# MIXR_Power_-_Regulators.net
KiCad netlist of a schematic drawn in Altium Designer
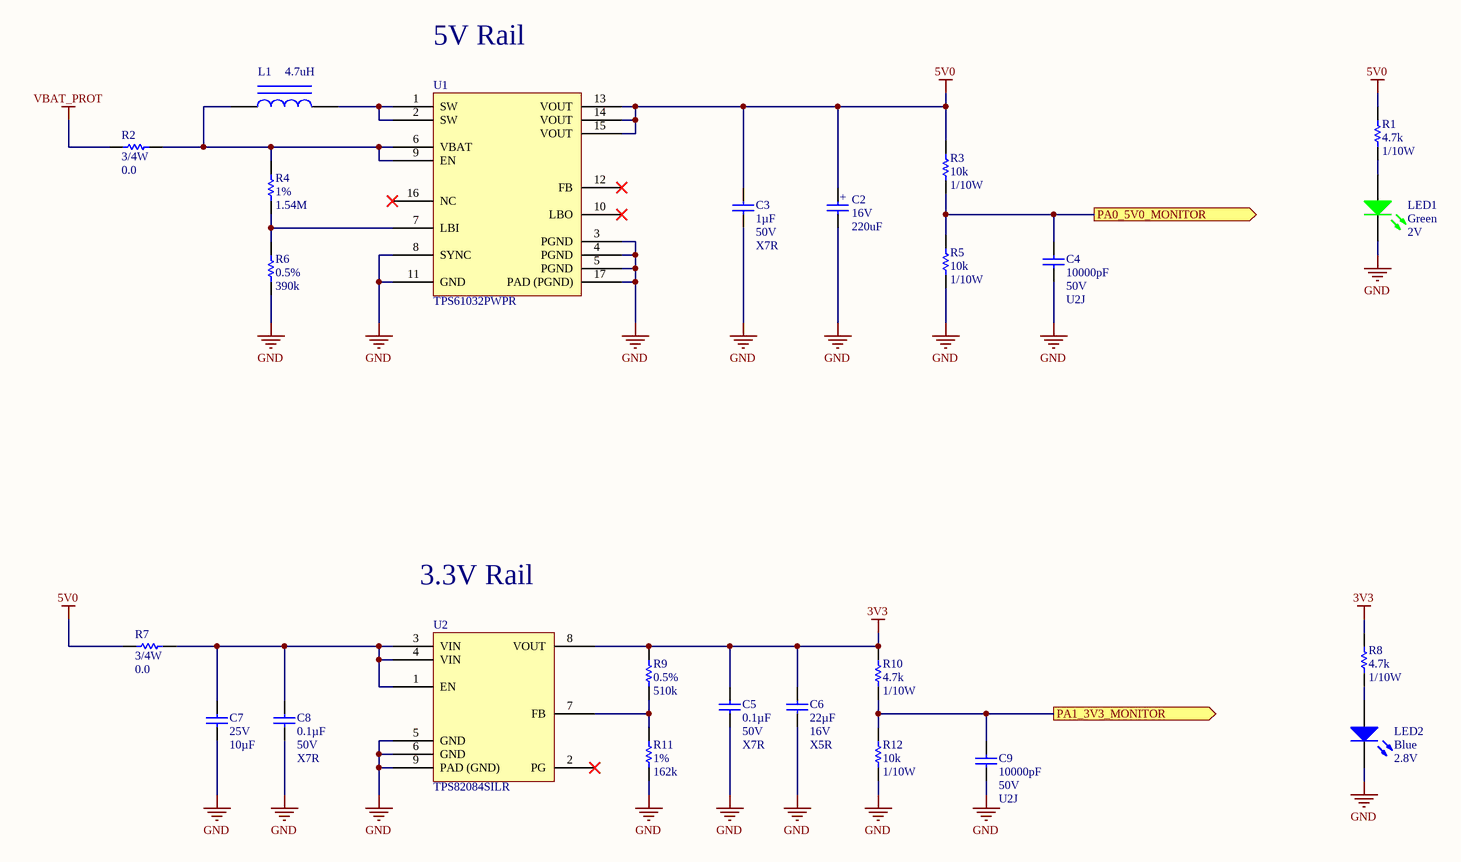
[diagram p0: MIXR Power - Regulators.SchDoc]

(export (version "E")
  (design (tool "Eeschema 10.0.6"))
  (components
    (comp (ref "C2")
      (value "CAP ALUM 220UF 20% 16V SMD")
      (footprint "CAP ALUM 6.3MM RADIAL SMD")
      (description "220µF 16V Aluminum Electrolytic Capacitors Radial, Can - SMD 2000 Hrs @ 85°C")
      (fields
        (field (name "MANUFACTURER") "Panasonic")
        (field (name "TOLERANCE") "20%")
        (field (name "VOLTAGE") "16V")
        (field (name "CAPACITANCE") "220uF")
      )
      (libsource (lib "Schematic Diagrams") (part "CAP ALUM 220UF 20% 16V SMD"))
    )
    (comp (ref "C3")
      (value "CAP CER 1UF 50V 10% X7R 0603")
      (footprint "CAP, 0603")
      (description "1µF ±10% 50V Ceramic Capacitor X7R 0603 (1608 Metric)")
      (fields
        (field (name "TOLERANCE") "±10%")
        (field (name "CAPACITANCE") "1µF")
        (field (name "VOLTAGE") "50V")
        (field (name "TEMPERATURE COEFFICIENT") "X7R")
      )
      (libsource (lib "Schematic Diagrams") (part "CAP CER 1UF 50V 10% X7R 0603"))
    )
    (comp (ref "C4")
      (value "CAP CER 10nF 50V 5% X7R 0603")
      (footprint "CAP, 0603")
      (description "10000pF ±5% 50V Ceramic Capacitor U2J 0603 (1608 Metric)")
      (fields
        (field (name "TOLERANCE") "±5%")
        (field (name "CAPACITANCE") "10000pF")
        (field (name "VOLTAGE") "50V")
        (field (name "TEMPERATURE COEFFICIENT") "U2J")
      )
      (libsource (lib "Schematic Diagrams") (part "CAP CER 10nF 50V 5% X7R 0603"))
    )
    (comp (ref "C5")
      (value "CAP CER 0.1UF 50V 10% X7R 0603")
      (footprint "CAP, 0603")
      (description "0.10µF ±10% 50V Ceramic Capacitor X7R 0603 (1608 Metric)")
      (fields
        (field (name "TOLERANCE") "±10%")
        (field (name "CAPACITANCE") "0.1µF")
        (field (name "VOLTAGE") "50V")
        (field (name "TEMPERATURE COEFFICIENT") "X7R")
      )
      (libsource (lib "Schematic Diagrams") (part "CAP CER 0.1UF 50V 10% X7R 0603"))
    )
    (comp (ref "C6")
      (value "CAP CER 22UF 16V ±20% X5R 1210")
      (footprint "CAP, 1210")
      (description "22µF ±20% 16V Ceramic Capacitor X5R 1210 (3225 Metric)")
      (fields
        (field (name "TOLERANCE") "±20%")
        (field (name "CAPACITANCE") "22µF")
        (field (name "VOLTAGE") "16V")
        (field (name "TEMPERATURE COEFFICIENT") "X5R")
      )
      (libsource (lib "Schematic Diagrams") (part "CAP CER 22UF 16V ±20% X5R 1210"))
    )
    (comp (ref "C7")
      (value "CAP CER 10uF 25V 10% X5R 0805")
      (footprint "CAP, 0805")
      (description "10µF ±10% 25V Ceramic Capacitor X5R 0805 (2012 Metric)")
      (fields
        (field (name "MANUFACTURER") "Murata Electronics North America")
        (field (name "MANUFACTURER PART NUMBER") "GRM21BR61E106KA73L")
        (field (name "VOLTAGE - RATED") "25V")
        (field (name "CAPACITANCE") "10µF")
      )
      (libsource (lib "Schematic Diagrams") (part "CAP CER 10uF 25V 10% X5R 0805"))
    )
    (comp (ref "C8")
      (value "CAP CER 0.1UF 50V 10% X7R 0603")
      (footprint "CAP, 0603")
      (description "0.10µF ±10% 50V Ceramic Capacitor X7R 0603 (1608 Metric)")
      (fields
        (field (name "TOLERANCE") "±10%")
        (field (name "CAPACITANCE") "0.1µF")
        (field (name "VOLTAGE") "50V")
        (field (name "TEMPERATURE COEFFICIENT") "X7R")
      )
      (libsource (lib "Schematic Diagrams") (part "CAP CER 0.1UF 50V 10% X7R 0603"))
    )
    (comp (ref "C9")
      (value "CAP CER 10nF 50V 5% X7R 0603")
      (footprint "CAP, 0603")
      (description "10000pF ±5% 50V Ceramic Capacitor U2J 0603 (1608 Metric)")
      (fields
        (field (name "TOLERANCE") "±5%")
        (field (name "CAPACITANCE") "10000pF")
        (field (name "VOLTAGE") "50V")
        (field (name "TEMPERATURE COEFFICIENT") "U2J")
      )
      (libsource (lib "Schematic Diagrams") (part "CAP CER 10nF 50V 5% X7R 0603"))
    )
    (comp (ref "L1")
      (value "IND 4.7uH 9.4A 10% SMD")
      (footprint "IND 4.7uH 9.4A 10% SMD")
      (description "Fixed Inductors SER1360 High Current 4.7 uH 10 % 9.4 A")
      (fields
        (field (name "MANUFACTURER") "Coilcraft")
        (field (name "TOLERANCE") "10%")
        (field (name "INDUCTANCE") "4.7uH")
      )
      (libsource (lib "Schematic Diagrams") (part "IND 4.7uH 9.4A 10% SMD"))
    )
    (comp (ref "LED1")
      (value "LED GREEN CLEAR 2V 0603")
      (footprint "LED_0603")
      (description "Green 572nm LED Indication - Discrete 2V 0603 (1608 Metric)")
      (fields
        (field (name "MANUFACTURER") "Wurth Electronics Inc.")
        (field (name "MANUFACTURER PART NUMBER") "150060VS75000")
        (field (name "COLOR") "Green")
        (field (name "VOLTAGE - FORWARD (VF) (TYP)") "2V")
      )
      (libsource (lib "Schematic Diagrams") (part "LED GREEN CLEAR 2V 0603"))
    )
    (comp (ref "LED2")
      (value "LED BLUE CLEAR 2.8V 0603")
      (footprint "LED_0603")
      (description "Blue 470nm LED Indication - Discrete 2.8V 0603 (1608 Metric)")
      (fields (field (name "COLOR") "Blue") (field (name "VOLTAGE - FORWARD (VF) (TYP)") "2.8V"))
      (libsource (lib "Schematic Diagrams") (part "LED BLUE CLEAR 2.8V 0603"))
    )
    (comp (ref "R1")
      (value "RES 4.7K OHM 1% 1/10W 0603")
      (footprint "RES, 0603")
      (description "4.7k Ohm ±1% 0.1W, 1/10W Chip Resistor 0603 (1608 Metric) Moisture Resistant Thick Film")
      (fields
        (field (name "TOLERANCE") "±1%")
        (field (name "RESISTANCE (OHMS)") "4.7k")
        (field (name "POWER (WATTS)") "1/10W")
      )
      (libsource (lib "Schematic Diagrams") (part "RES 4.7K OHM 1% 1/10W 0603"))
    )
    (comp (ref "R2")
      (value "RES 0.0 OHM 3/4W 1206")
      (footprint "RES 1206")
      (description "0 Ohms Jumper 0.75W, 3/4W Chip Resistor 1206 (3216 Metric) Automotive AEC-Q200 Metal Foil")
      (fields
        (field (name "MANUFACTURER") "Stackpole Electronics Inc.")
        (field (name "MANUFACTURER PART NUMBER") "HCJ1206ZT0R00")
        (field (name "POWER (WATTS)") "3/4W")
        (field (name "RESISTANCE") "0.0")
      )
      (libsource (lib "Schematic Diagrams") (part "RES 0.0 OHM 3/4W 1206"))
    )
    (comp (ref "R3")
      (value "RES 10K OHM 1% 1/10W 0603")
      (footprint "RES, 0603")
      (description "RES SMD 10K OHM 1% 1/10W 0603")
      (fields
        (field (name "TOLERANCE") "±1%")
        (field (name "RESISTANCE") "10k")
        (field (name "POWER") "1/10W")
      )
      (libsource (lib "Schematic Diagrams") (part "RES 10K OHM 1% 1/10W 0603"))
    )
    (comp (ref "R4")
      (value "RES 1.54M OHM 1% 1/10W 0603")
      (footprint "RES, 0603")
      (fields
        (field (name "MANUFACTURER") "Vishay")
        (field (name "MANUFACTURER PART NUMBER") "CRCW06031M54FKEA")
        (field (name "TOLERANCE") "1%")
        (field (name "RESISTANCE") "1.54M")
      )
      (libsource (lib "Schematic Diagrams") (part "RES 1.54M OHM 1% 1/10W 0603"))
    )
    (comp (ref "R5")
      (value "RES 10K OHM 1% 1/10W 0603")
      (footprint "RES, 0603")
      (description "RES SMD 10K OHM 1% 1/10W 0603")
      (fields
        (field (name "TOLERANCE") "±1%")
        (field (name "RESISTANCE") "10k")
        (field (name "POWER") "1/10W")
      )
      (libsource (lib "Schematic Diagrams") (part "RES 10K OHM 1% 1/10W 0603"))
    )
    (comp (ref "R6")
      (value "RES 390K OHM 1% 1/10W 0603")
      (footprint "RES, 0603")
      (description "390 kOhms ±0.5% 0.1W, 1/10W Chip Resistor 0603 (1608 Metric) Thin Film")
      (fields
        (field (name "MANUFACTURER") "Yageo")
        (field (name "MANUFACTURER PART NUMBER") "RT0603DRE07390KL")
        (field (name "TOLERANCE") "0.5%")
        (field (name "RESISTANCE") "390k")
      )
      (libsource (lib "Schematic Diagrams") (part "RES 390K OHM 1% 1/10W 0603"))
    )
    (comp (ref "R7")
      (value "RES 0.0 OHM 3/4W 1206")
      (footprint "RES 1206")
      (description "0 Ohms Jumper 0.75W, 3/4W Chip Resistor 1206 (3216 Metric) Automotive AEC-Q200 Metal Foil")
      (fields
        (field (name "MANUFACTURER") "Stackpole Electronics Inc.")
        (field (name "MANUFACTURER PART NUMBER") "HCJ1206ZT0R00")
        (field (name "POWER (WATTS)") "3/4W")
        (field (name "RESISTANCE") "0.0")
      )
      (libsource (lib "Schematic Diagrams") (part "RES 0.0 OHM 3/4W 1206"))
    )
    (comp (ref "R8")
      (value "RES 4.7K OHM 1% 1/10W 0603")
      (footprint "RES, 0603")
      (description "4.7k Ohm ±1% 0.1W, 1/10W Chip Resistor 0603 (1608 Metric) Moisture Resistant Thick Film")
      (fields
        (field (name "TOLERANCE") "±1%")
        (field (name "RESISTANCE (OHMS)") "4.7k")
        (field (name "POWER (WATTS)") "1/10W")
      )
      (libsource (lib "Schematic Diagrams") (part "RES 4.7K OHM 1% 1/10W 0603"))
    )
    (comp (ref "R9")
      (value "RES 510K OHM 0.5% 1/10W 0603")
      (footprint "RES, 0603")
      (description "510 kOhms ±0.5% 0.1W, 1/10W Chip Resistor 0603 (1608 Metric) Thin Film")
      (fields
        (field (name "MANUFACTURER") "Yageo")
        (field (name "MANUFACTURER PART NUMBER") "RT0603DRE07510KL")
        (field (name "TOLERANCE") "0.5%")
        (field (name "RESISTANCE") "510k")
      )
      (libsource (lib "Schematic Diagrams") (part "RES 510K OHM 0.5% 1/10W 0603"))
    )
    (comp (ref "R10")
      (value "RES 4.7K OHM 1% 1/10W 0603")
      (footprint "RES, 0603")
      (description "4.7k Ohm ±1% 0.1W, 1/10W Chip Resistor 0603 (1608 Metric) Moisture Resistant Thick Film")
      (fields
        (field (name "TOLERANCE") "±1%")
        (field (name "RESISTANCE (OHMS)") "4.7k")
        (field (name "POWER (WATTS)") "1/10W")
      )
      (libsource (lib "Schematic Diagrams") (part "RES 4.7K OHM 1% 1/10W 0603"))
    )
    (comp (ref "R11")
      (value "RES 162K OHM 1% 1/10W 0603")
      (footprint "RES, 0603")
      (description "162 kOhms ±1% 0.1W, 1/10W Chip Resistor 0603 (1608 Metric) Moisture Resistant Thick Film")
      (fields
        (field (name "MANUFACTURER") "Yageo")
        (field (name "MANUFACTURER PART NUMBER") "RC0603FR-07162KL")
        (field (name "TOLERANCE") "1%")
        (field (name "RESISTANCE") "162k")
      )
      (libsource (lib "Schematic Diagrams") (part "RES 162K OHM 1% 1/10W 0603"))
    )
    (comp (ref "R12")
      (value "RES 10K OHM 1% 1/10W 0603")
      (footprint "RES, 0603")
      (description "RES SMD 10K OHM 1% 1/10W 0603")
      (fields
        (field (name "TOLERANCE") "±1%")
        (field (name "RESISTANCE") "10k")
        (field (name "POWER") "1/10W")
      )
      (libsource (lib "Schematic Diagrams") (part "RES 10K OHM 1% 1/10W 0603"))
    )
    (comp (ref "U1")
      (value "IC REG BOOST 5V 3.6A 16-TSSOP")
      (footprint "IC REG BOOST 5V 3.6A 16-TSSOP")
      (fields
        (field (name "MANUFACTURER") "Texas Instruments")
        (field (name "MANUFACTURER PART NUMBER") "TPS61032PWPR")
      )
      (libsource (lib "Schematic Diagrams") (part "IC REG BOOST 5V 3.6A 16-TSSOP"))
    )
    (comp (ref "U2")
      (value "IC DCDC 0.8-6V 2A 8-uSIP")
      (footprint "IC DCDC 0.8-6V 2A 8-uSIP")
      (description "Non-Isolated PoL Module DC DC Converter 1 Output 0.8 ~ 6V 2A 2.5V - 6V Input")
      (fields
        (field (name "MANUFACTURER") "Texas Instruments")
        (field (name "MANUFACTURER PART NUMBER") "TPS82084SILR")
      )
      (libsource (lib "Schematic Diagrams") (part "IC DCDC 0.8-6V 2A 8-uSIP"))
    )
  )
  (nets
    (net (code "1") (name "/PA0_5V0_MONITOR") (class "Default")
      (node (ref "C4") (pin "1") (pinfunction "1_1") (pintype "passive"))
      (node (ref "R3") (pin "2") (pinfunction "2_2") (pintype "passive"))
      (node (ref "R5") (pin "1") (pinfunction "1_1") (pintype "passive"))
    )
    (net (code "2") (name "/PA1_3V3_MONITOR") (class "Default")
      (node (ref "C9") (pin "1") (pinfunction "1_1") (pintype "passive"))
      (node (ref "R10") (pin "2") (pinfunction "2_2") (pintype "passive"))
      (node (ref "R12") (pin "1") (pinfunction "1_1") (pintype "passive"))
    )
    (net (code "3") (name "3V3") (class "Default")
      (node (ref "C5") (pin "1") (pinfunction "1_1") (pintype "passive"))
      (node (ref "C6") (pin "1") (pinfunction "1_1") (pintype "passive"))
      (node (ref "R10") (pin "1") (pinfunction "1_1") (pintype "passive"))
      (node (ref "R8") (pin "1") (pinfunction "1_1") (pintype "passive"))
      (node (ref "R9") (pin "1") (pinfunction "1_1") (pintype "passive"))
      (node (ref "U2") (pin "8") (pinfunction "VOUT_8") (pintype "passive"))
    )
    (net (code "4") (name "5V0") (class "Default")
      (node (ref "C2") (pin "1") (pinfunction "1_1") (pintype "passive"))
      (node (ref "C3") (pin "1") (pinfunction "1_1") (pintype "passive"))
      (node (ref "R1") (pin "1") (pinfunction "1_1") (pintype "passive"))
      (node (ref "R3") (pin "1") (pinfunction "1_1") (pintype "passive"))
      (node (ref "R7") (pin "1") (pinfunction "1_1") (pintype "passive"))
      (node (ref "U1") (pin "13") (pinfunction "VOUT_13") (pintype "passive"))
      (node (ref "U1") (pin "14") (pinfunction "VOUT_14") (pintype "passive"))
      (node (ref "U1") (pin "15") (pinfunction "VOUT_15") (pintype "passive"))
    )
    (net (code "5") (name "GND") (class "Default")
      (node (ref "C2") (pin "2") (pinfunction "2_2") (pintype "passive"))
      (node (ref "C3") (pin "2") (pinfunction "2_2") (pintype "passive"))
      (node (ref "C4") (pin "2") (pinfunction "2_2") (pintype "passive"))
      (node (ref "C5") (pin "2") (pinfunction "2_2") (pintype "passive"))
      (node (ref "C6") (pin "2") (pinfunction "2_2") (pintype "passive"))
      (node (ref "C7") (pin "2") (pinfunction "2_2") (pintype "passive"))
      (node (ref "C8") (pin "2") (pinfunction "2_2") (pintype "passive"))
      (node (ref "C9") (pin "2") (pinfunction "2_2") (pintype "passive"))
      (node (ref "LED1") (pin "2") (pinfunction "K_2") (pintype "passive"))
      (node (ref "LED2") (pin "2") (pinfunction "K_2") (pintype "passive"))
      (node (ref "R11") (pin "2") (pinfunction "2_2") (pintype "passive"))
      (node (ref "R12") (pin "2") (pinfunction "2_2") (pintype "passive"))
      (node (ref "R5") (pin "2") (pinfunction "2_2") (pintype "passive"))
      (node (ref "R6") (pin "2") (pinfunction "2_2") (pintype "passive"))
      (node (ref "U1") (pin "11") (pinfunction "GND_11") (pintype "passive"))
      (node (ref "U1") (pin "17") (pinfunction "PAD_(PGND)_17") (pintype "passive"))
      (node (ref "U1") (pin "3") (pinfunction "PGND_3") (pintype "passive"))
      (node (ref "U1") (pin "4") (pinfunction "PGND_4") (pintype "passive"))
      (node (ref "U1") (pin "5") (pinfunction "PGND_5") (pintype "passive"))
      (node (ref "U1") (pin "8") (pinfunction "SYNC_8") (pintype "passive"))
      (node (ref "U2") (pin "5") (pinfunction "GND_5") (pintype "passive"))
      (node (ref "U2") (pin "6") (pinfunction "GND_6") (pintype "passive"))
      (node (ref "U2") (pin "9") (pinfunction "PAD_(GND)_9") (pintype "passive"))
    )
    (net (code "6") (name "Net-(L1-Pad2)") (class "Default")
      (node (ref "L1") (pin "2") (pinfunction "2_2") (pintype "passive"))
      (node (ref "U1") (pin "1") (pinfunction "SW_1") (pintype "passive"))
      (node (ref "U1") (pin "2") (pinfunction "SW_2") (pintype "passive"))
    )
    (net (code "7") (name "Net-(LED1-A)") (class "Default")
      (node (ref "LED1") (pin "1") (pinfunction "A_1") (pintype "passive"))
      (node (ref "R1") (pin "2") (pinfunction "2_2") (pintype "passive"))
    )
    (net (code "8") (name "Net-(LED2-A)") (class "Default")
      (node (ref "LED2") (pin "1") (pinfunction "A_1") (pintype "passive"))
      (node (ref "R8") (pin "2") (pinfunction "2_2") (pintype "passive"))
    )
    (net (code "9") (name "Net-(U1-EN)") (class "Default")
      (node (ref "L1") (pin "1") (pinfunction "1_1") (pintype "passive"))
      (node (ref "R2") (pin "2") (pinfunction "2_2") (pintype "passive"))
      (node (ref "R4") (pin "1") (pinfunction "1_1") (pintype "passive"))
      (node (ref "U1") (pin "6") (pinfunction "VBAT_6") (pintype "passive"))
      (node (ref "U1") (pin "9") (pinfunction "EN_9") (pintype "passive"))
    )
    (net (code "10") (name "Net-(U1-LBI)") (class "Default")
      (node (ref "R4") (pin "2") (pinfunction "2_2") (pintype "passive"))
      (node (ref "R6") (pin "1") (pinfunction "1_1") (pintype "passive"))
      (node (ref "U1") (pin "7") (pinfunction "LBI_7") (pintype "passive"))
    )
    (net (code "11") (name "Net-(U2-EN)") (class "Default")
      (node (ref "C7") (pin "1") (pinfunction "1_1") (pintype "passive"))
      (node (ref "C8") (pin "1") (pinfunction "1_1") (pintype "passive"))
      (node (ref "R7") (pin "2") (pinfunction "2_2") (pintype "passive"))
      (node (ref "U2") (pin "1") (pinfunction "EN_1") (pintype "passive"))
      (node (ref "U2") (pin "3") (pinfunction "VIN_3") (pintype "passive"))
      (node (ref "U2") (pin "4") (pinfunction "VIN_4") (pintype "passive"))
    )
    (net (code "12") (name "Net-(U2-FB)") (class "Default")
      (node (ref "R11") (pin "1") (pinfunction "1_1") (pintype "passive"))
      (node (ref "R9") (pin "2") (pinfunction "2_2") (pintype "passive"))
      (node (ref "U2") (pin "7") (pinfunction "FB_7") (pintype "passive"))
    )
    (net (code "13") (name "VBAT_PROT") (class "Default")
      (node (ref "R2") (pin "1") (pinfunction "1_1") (pintype "passive"))
    )
    (net (code "14") (name "unconnected-(U1-FB-Pad12)") (class "Default")
      (node (ref "U1") (pin "12") (pinfunction "FB_12") (pintype "passive+no_connect"))
    )
    (net (code "15") (name "unconnected-(U1-LBO-Pad10)") (class "Default")
      (node (ref "U1") (pin "10") (pinfunction "LBO_10") (pintype "passive+no_connect"))
    )
    (net (code "16") (name "unconnected-(U1-NC-Pad16)") (class "Default")
      (node (ref "U1") (pin "16") (pinfunction "NC_16") (pintype "passive+no_connect"))
    )
    (net (code "17") (name "unconnected-(U2-PG-Pad2)") (class "Default")
      (node (ref "U2") (pin "2") (pinfunction "PG_2") (pintype "passive+no_connect"))
    )
  )
)
